# Schaltplan_6011057_Tamme.net
KiCad netlist of a schematic drawn in EAGLE
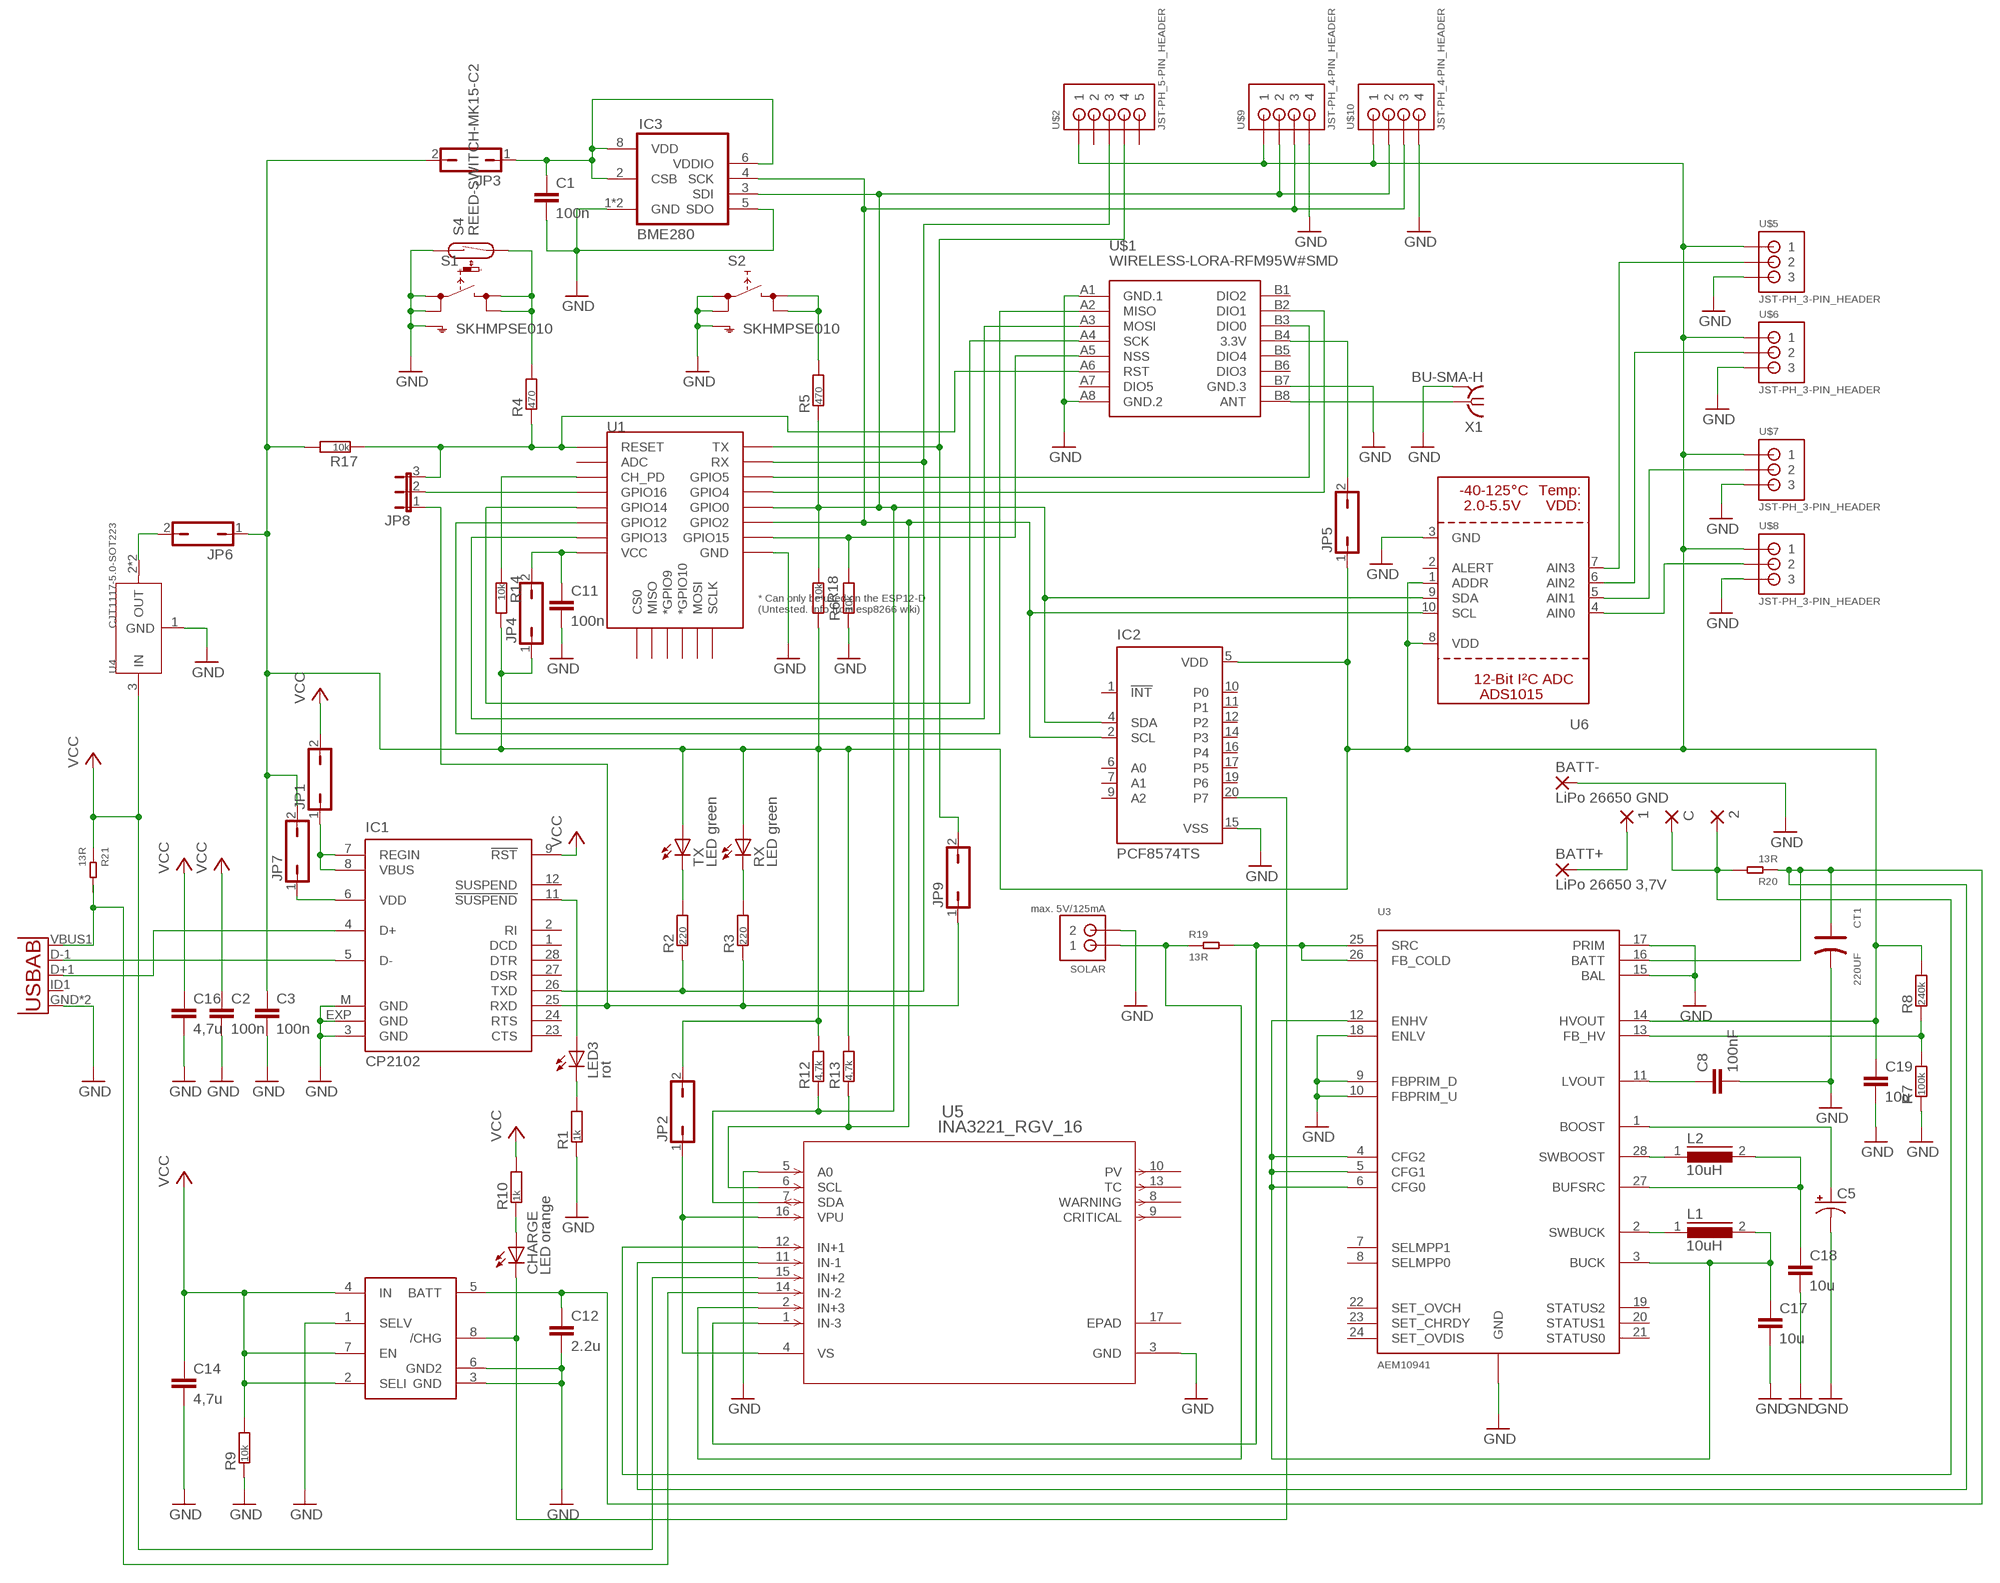
[diagram p0: schematic, sheet 1]

(export (version "E")
  (design (tool "Eeschema 10.0.6"))
  (components
    (comp (ref "1")
      (value "WIREPAD2,54/1,0")
      (footprint "eagle-import:2,54_1,0")
      (libsource (lib "eagle-import") (part "WIREPAD2,54/1,0"))
    )
    (comp (ref "2")
      (value "WIREPAD2,54/1,0")
      (footprint "eagle-import:2,54_1,0")
      (libsource (lib "eagle-import") (part "WIREPAD2,54/1,0"))
    )
    (comp (ref "BATT+")
      (value "LiPo 26650 3,7V")
      (footprint "eagle-import:4,16O1,6")
      (libsource (lib "eagle-import") (part "WIREPAD4,16O1,6"))
    )
    (comp (ref "BATT-")
      (value "LiPo 26650 GND")
      (footprint "eagle-import:4,16O1,6")
      (libsource (lib "eagle-import") (part "WIREPAD4,16O1,6"))
    )
    (comp (ref "C")
      (value "WIREPAD2,54/1,0")
      (footprint "eagle-import:2,54_1,0")
      (libsource (lib "eagle-import") (part "WIREPAD2,54/1,0"))
    )
    (comp (ref "C1")
      (value "100n")
      (footprint "eagle-import:RESC0805_M")
      (libsource (lib "eagle-import") (part "CAPACITOR_0805_M"))
    )
    (comp (ref "C2")
      (value "100n")
      (footprint "eagle-import:RESC0805_M")
      (libsource (lib "eagle-import") (part "CAPACITOR_0805_M"))
    )
    (comp (ref "C3")
      (value "100n")
      (footprint "eagle-import:RESC0805_M")
      (libsource (lib "eagle-import") (part "CAPACITOR_0805_M"))
    )
    (comp (ref "C5")
      (value "CPOL-USB/3528-21W")
      (footprint "eagle-import:B_3528-21W")
      (libsource (lib "eagle-import") (part "CPOL-USB/3528-21W"))
    )
    (comp (ref "C8")
      (value "100nF")
      (footprint "eagle-import:C1206")
      (libsource (lib "eagle-import") (part "CC1206"))
    )
    (comp (ref "C11")
      (value "100n")
      (footprint "eagle-import:RESC0805_M")
      (libsource (lib "eagle-import") (part "CAPACITOR_0805_M"))
    )
    (comp (ref "C12")
      (value "2.2u")
      (footprint "eagle-import:C1812")
      (libsource (lib "eagle-import") (part "C-EUC1812"))
    )
    (comp (ref "C14")
      (value "4,7u")
      (footprint "eagle-import:C1812")
      (libsource (lib "eagle-import") (part "C-EUC1812"))
    )
    (comp (ref "C16")
      (value "4,7u")
      (footprint "eagle-import:C1812")
      (libsource (lib "eagle-import") (part "C-EUC1812"))
    )
    (comp (ref "C17")
      (value "10u")
      (footprint "eagle-import:C1812")
      (libsource (lib "eagle-import") (part "C-EUC1812"))
    )
    (comp (ref "C18")
      (value "10u")
      (footprint "eagle-import:C1812")
      (libsource (lib "eagle-import") (part "C-EUC1812"))
    )
    (comp (ref "C19")
      (value "10u")
      (footprint "eagle-import:C1812")
      (libsource (lib "eagle-import") (part "C-EUC1812"))
    )
    (comp (ref "CHARGE")
      (value "LED orange")
      (footprint "eagle-import:1206")
      (libsource (lib "eagle-import") (part "LEDSMT1206"))
    )
    (comp (ref "CT1")
      (value "220UF")
      (footprint "eagle-import:ELECTRO-SMD-C-6MM")
      (fields (field (name "MPN") "CS1E221M-CRE77"))
      (libsource (lib "eagle-import") (part "ALUMINUM-SMD-220UF-16V(D6.3-H7.7MM)"))
    )
    (comp (ref "IC1")
      (value "CP2102")
      (footprint "eagle-import:MLP28")
      (fields (field (name "MF") "FARNELL") (field (name "MPN") "CP2102-GM"))
      (libsource (lib "eagle-import") (part "CP2102"))
    )
    (comp (ref "IC2")
      (value "PCF8574TS")
      (footprint "eagle-import:SSOP20")
      (fields (field (name "MPN") "PCF8574TS/3,118"))
      (libsource (lib "eagle-import") (part "PCF8574TS"))
    )
    (comp (ref "IC3")
      (value "BME280")
      (footprint "eagle-import:BME280")
      (libsource (lib "eagle-import") (part "BME280"))
    )
    (comp (ref "JP1")
      (value "JP1Q")
      (footprint "eagle-import:JP1")
      (libsource (lib "eagle-import") (part "JP1Q"))
    )
    (comp (ref "JP2")
      (value "JP1Q")
      (footprint "eagle-import:JP1")
      (libsource (lib "eagle-import") (part "JP1Q"))
    )
    (comp (ref "JP3")
      (value "JP1Q")
      (footprint "eagle-import:JP1")
      (libsource (lib "eagle-import") (part "JP1Q"))
    )
    (comp (ref "JP4")
      (value "JP1Q")
      (footprint "eagle-import:JP1")
      (libsource (lib "eagle-import") (part "JP1Q"))
    )
    (comp (ref "JP5")
      (value "JP1Q")
      (footprint "eagle-import:JP1")
      (libsource (lib "eagle-import") (part "JP1Q"))
    )
    (comp (ref "JP6")
      (value "JP1Q")
      (footprint "eagle-import:JP1")
      (libsource (lib "eagle-import") (part "JP1Q"))
    )
    (comp (ref "JP7")
      (value "JP1Q")
      (footprint "eagle-import:JP1")
      (libsource (lib "eagle-import") (part "JP1Q"))
    )
    (comp (ref "JP8")
      (value "JP2E")
      (footprint "eagle-import:JP2")
      (libsource (lib "eagle-import") (part "JP2E"))
    )
    (comp (ref "JP9")
      (value "JP1Q")
      (footprint "eagle-import:JP1")
      (libsource (lib "eagle-import") (part "JP1Q"))
    )
    (comp (ref "L1")
      (value "10uH")
      (footprint "eagle-import:DR74")
      (libsource (lib "eagle-import") (part "DR74"))
    )
    (comp (ref "L2")
      (value "10uH")
      (footprint "eagle-import:DR74")
      (libsource (lib "eagle-import") (part "DR74"))
    )
    (comp (ref "LED3")
      (value "rot")
      (footprint "eagle-import:1206")
      (libsource (lib "eagle-import") (part "LEDSMT1206"))
    )
    (comp (ref "R1")
      (value "1k")
      (footprint "eagle-import:RESC0805_M")
      (libsource (lib "eagle-import") (part "RESISTOR_0805_M"))
    )
    (comp (ref "R2")
      (value "220")
      (footprint "eagle-import:RESC0805_M")
      (libsource (lib "eagle-import") (part "RESISTOR_0805_M"))
    )
    (comp (ref "R3")
      (value "220")
      (footprint "eagle-import:RESC0805_M")
      (libsource (lib "eagle-import") (part "RESISTOR_0805_M"))
    )
    (comp (ref "R4")
      (value "470")
      (footprint "eagle-import:RESC0805_M")
      (libsource (lib "eagle-import") (part "RESISTOR_0805_M"))
    )
    (comp (ref "R5")
      (value "470")
      (footprint "eagle-import:RESC0805_M")
      (libsource (lib "eagle-import") (part "RESISTOR_0805_M"))
    )
    (comp (ref "R6")
      (value "10k")
      (footprint "eagle-import:RESC0805_M")
      (libsource (lib "eagle-import") (part "RESISTOR_0805_M"))
    )
    (comp (ref "R7")
      (value "100k")
      (footprint "eagle-import:RESC0805_M")
      (libsource (lib "eagle-import") (part "RESISTOR_0805_M"))
    )
    (comp (ref "R8")
      (value "240k")
      (footprint "eagle-import:RESC0805_M")
      (libsource (lib "eagle-import") (part "RESISTOR_0805_M"))
    )
    (comp (ref "R9")
      (value "10k")
      (footprint "eagle-import:RESC0805_M")
      (libsource (lib "eagle-import") (part "RESISTOR_0805_M"))
    )
    (comp (ref "R10")
      (value "1k")
      (footprint "eagle-import:RESC0805_M")
      (libsource (lib "eagle-import") (part "RESISTOR_0805_M"))
    )
    (comp (ref "R12")
      (value "4,7k")
      (footprint "eagle-import:RESC0805_M")
      (libsource (lib "eagle-import") (part "RESISTOR_0805_M"))
    )
    (comp (ref "R13")
      (value "4,7k")
      (footprint "eagle-import:RESC0805_M")
      (libsource (lib "eagle-import") (part "RESISTOR_0805_M"))
    )
    (comp (ref "R14")
      (value "10k")
      (footprint "eagle-import:RESC0805_M")
      (libsource (lib "eagle-import") (part "RESISTOR_0805_M"))
    )
    (comp (ref "R17")
      (value "10k")
      (footprint "eagle-import:RESC0805_M")
      (libsource (lib "eagle-import") (part "RESISTOR_0805_M"))
    )
    (comp (ref "R18")
      (value "10k")
      (footprint "eagle-import:RESC0805_M")
      (libsource (lib "eagle-import") (part "RESISTOR_0805_M"))
    )
    (comp (ref "R19")
      (value "13R")
      (footprint "eagle-import:R1206")
      (fields (field (name "MPN") "RC1206JR-0713RL"))
      (libsource (lib "eagle-import") (part "SMD-RES-13R-5%-1/4W(1206)"))
    )
    (comp (ref "R20")
      (value "13R")
      (footprint "eagle-import:R1206")
      (fields (field (name "MPN") "RC1206JR-0713RL"))
      (libsource (lib "eagle-import") (part "SMD-RES-13R-5%-1/4W(1206)"))
    )
    (comp (ref "R21")
      (value "13R")
      (footprint "eagle-import:R1206")
      (fields (field (name "MPN") "RC1206JR-0713RL"))
      (libsource (lib "eagle-import") (part "SMD-RES-13R-5%-1/4W(1206)"))
    )
    (comp (ref "RX")
      (value "LED green")
      (footprint "eagle-import:1206")
      (libsource (lib "eagle-import") (part "LEDSMT1206"))
    )
    (comp (ref "S1")
      (value "SKHMPSE010")
      (footprint "eagle-import:SKHMPXE010")
      (libsource (lib "eagle-import") (part "SKHMPE010S"))
    )
    (comp (ref "S2")
      (value "SKHMPSE010")
      (footprint "eagle-import:SKHMPXE010")
      (libsource (lib "eagle-import") (part "SKHMPE010S"))
    )
    (comp (ref "S4")
      (value "REED-SWITCH-MK15-C2")
      (footprint "eagle-import:MK15")
      (fields (field (name "MF") "MEDER") (field (name "MPN") "MK15-C-2"))
      (libsource (lib "eagle-import") (part "REED-SWITCH-MK15-C2"))
    )
    (comp (ref "SOLAR")
      (value "max. 5V/125mA")
      (footprint "eagle-import:JST_B2B-PH_HEADER")
      (libsource (lib "eagle-import") (part "JST-PH_2-PIN_HEADER"))
    )
    (comp (ref "TX")
      (value "LED green")
      (footprint "eagle-import:1206")
      (libsource (lib "eagle-import") (part "LEDSMT1206"))
    )
    (comp (ref "U$1")
      (value "WIRELESS-LORA-RFM95W#SMD")
      (footprint "eagle-import:WIRELESS-LORA-RFM95W#SMD")
      (libsource (lib "eagle-import") (part "WIRELESS-LORA-RFM95W#SMD"))
    )
    (comp (ref "U$2")
      (value "JST-PH_5-PIN_HEADER")
      (footprint "eagle-import:JST_B5B-PH_HEADER")
      (libsource (lib "eagle-import") (part "JST-PH_5-PIN_HEADER"))
    )
    (comp (ref "U$3")
      (value "MAX1811SO8")
      (footprint "eagle-import:SO08")
      (libsource (lib "eagle-import") (part "MAX1811SO8"))
    )
    (comp (ref "U$5")
      (value "JST-PH_3-PIN_HEADER")
      (footprint "eagle-import:JST_B3B-PH_HEADER")
      (libsource (lib "eagle-import") (part "JST-PH_3-PIN_HEADER"))
    )
    (comp (ref "U$6")
      (value "JST-PH_3-PIN_HEADER")
      (footprint "eagle-import:JST_B3B-PH_HEADER")
      (libsource (lib "eagle-import") (part "JST-PH_3-PIN_HEADER"))
    )
    (comp (ref "U$7")
      (value "JST-PH_3-PIN_HEADER")
      (footprint "eagle-import:JST_B3B-PH_HEADER")
      (libsource (lib "eagle-import") (part "JST-PH_3-PIN_HEADER"))
    )
    (comp (ref "U$8")
      (value "JST-PH_3-PIN_HEADER")
      (footprint "eagle-import:JST_B3B-PH_HEADER")
      (libsource (lib "eagle-import") (part "JST-PH_3-PIN_HEADER"))
    )
    (comp (ref "U$9")
      (value "JST-PH_4-PIN_HEADER")
      (footprint "eagle-import:JST_B4B-PH_HEADER")
      (libsource (lib "eagle-import") (part "JST-PH_4-PIN_HEADER"))
    )
    (comp (ref "U$10")
      (value "JST-PH_4-PIN_HEADER")
      (footprint "eagle-import:JST_B4B-PH_HEADER")
      (libsource (lib "eagle-import") (part "JST-PH_4-PIN_HEADER"))
    )
    (comp (ref "U1")
      (value "ESP12ESMD")
      (footprint "eagle-import:ESP12E-SMD")
      (libsource (lib "eagle-import") (part "ESP12ESMD"))
    )
    (comp (ref "U2")
      (value "USB\"\"")
      (footprint "eagle-import:USB-MICRO-SMD")
      (libsource (lib "eagle-import") (part "USB{dblquote}{dblquote}"))
    )
    (comp (ref "U3")
      (value "AEM10941")
      (footprint "eagle-import:QFN28_5X5_05PITCH")
      (libsource (lib "eagle-import") (part "AEM10941"))
    )
    (comp (ref "U4")
      (value "CJT1117-5.0-SOT223")
      (footprint "eagle-import:SOT-223")
      (fields (field (name "MPN") "CJT1117-5.0"))
      (libsource (lib "eagle-import") (part "PMIC-CJT1117-5.0(SOT223)"))
    )
    (comp (ref "U5")
      (value "INA3221_RGV_16")
      (footprint "eagle-import:RGV16_2P16X2P16")
      (fields
        (field (name "GENERIC_PART_NUMBER") "INA3221")
        (field (name "MANUFACTURER") "Texas Instruments")
      )
      (libsource (lib "eagle-import") (part "INA3221_RGV_16"))
    )
    (comp (ref "U6")
      (value "ADC_ADS1015")
      (footprint "eagle-import:MSOP10")
      (libsource (lib "eagle-import") (part "ADC_ADS1015"))
    )
    (comp (ref "X1")
      (value "BU-SMA-H")
      (footprint "eagle-import:BU-SMA-H")
      (libsource (lib "eagle-import") (part "BU-SMA-H"))
    )
  )
  (nets
    (net (code "1") (name "GND") (class "Default")
      (node (ref "BATT-") (pin "1") (pinfunction "P_1") (pintype "passive"))
      (node (ref "C1") (pin "2") (pinfunction "2_2") (pintype "passive"))
      (node (ref "C11") (pin "2") (pinfunction "2_2") (pintype "passive"))
      (node (ref "C12") (pin "2") (pinfunction "2_2") (pintype "passive"))
      (node (ref "C14") (pin "2") (pinfunction "2_2") (pintype "passive"))
      (node (ref "C16") (pin "2") (pinfunction "2_2") (pintype "passive"))
      (node (ref "C17") (pin "2") (pinfunction "2_2") (pintype "passive"))
      (node (ref "C18") (pin "2") (pinfunction "2_2") (pintype "passive"))
      (node (ref "C19") (pin "2") (pinfunction "2_2") (pintype "passive"))
      (node (ref "C2") (pin "2") (pinfunction "2_2") (pintype "passive"))
      (node (ref "C3") (pin "2") (pinfunction "2_2") (pintype "passive"))
      (node (ref "C5") (pin "-") (pinfunction "-_-") (pintype "passive"))
      (node (ref "C8") (pin "2") (pinfunction "2_2") (pintype "passive"))
      (node (ref "CT1") (pin "-") (pinfunction "-_-") (pintype "passive"))
      (node (ref "IC1") (pin "3") (pinfunction "GND_3") (pintype "power_in"))
      (node (ref "IC1") (pin "EXP") (pinfunction "GND_EXP") (pintype "power_in"))
      (node (ref "IC1") (pin "M") (pinfunction "GND_M") (pintype "power_in"))
      (node (ref "IC2") (pin "15") (pinfunction "VSS_15") (pintype "power_in"))
      (node (ref "IC3") (pin "1") (pinfunction "GND_1") (pintype "power_in"))
      (node (ref "IC3") (pin "5") (pinfunction "SDO_5") (pintype "input"))
      (node (ref "IC3") (pin "7") (pinfunction "GND_7") (pintype "power_in"))
      (node (ref "R1") (pin "1") (pinfunction "1_1") (pintype "passive"))
      (node (ref "R6") (pin "1") (pinfunction "1_1") (pintype "passive"))
      (node (ref "R7") (pin "1") (pinfunction "1_1") (pintype "passive"))
      (node (ref "R9") (pin "1") (pinfunction "1_1") (pintype "passive"))
      (node (ref "S1") (pin "1") (pinfunction "1.1_1") (pintype "passive"))
      (node (ref "S1") (pin "2") (pinfunction "1.2_2") (pintype "passive"))
      (node (ref "S1") (pin "5") (pinfunction "SH_5") (pintype "passive"))
      (node (ref "S2") (pin "1") (pinfunction "1.1_1") (pintype "passive"))
      (node (ref "S2") (pin "2") (pinfunction "1.2_2") (pintype "passive"))
      (node (ref "S2") (pin "5") (pinfunction "SH_5") (pintype "passive"))
      (node (ref "S4") (pin "1") (pinfunction "1_1") (pintype "passive"))
      (node (ref "SOLAR") (pin "P2") (pinfunction "2_P2") (pintype "bidirectional"))
      (node (ref "U$1") (pin "A1") (pinfunction "GND.1_A1") (pintype "power_in"))
      (node (ref "U$1") (pin "A8") (pinfunction "GND.2_A8") (pintype "power_in"))
      (node (ref "U$1") (pin "B7") (pinfunction "GND.3_B7") (pintype "power_in"))
      (node (ref "U$10") (pin "P4") (pinfunction "4_P4") (pintype "bidirectional"))
      (node (ref "U$3") (pin "1") (pinfunction "SELV_1") (pintype "bidirectional"))
      (node (ref "U$3") (pin "3") (pinfunction "GND_3") (pintype "bidirectional"))
      (node (ref "U$3") (pin "6") (pinfunction "GND2_6") (pintype "bidirectional"))
      (node (ref "U$5") (pin "P3") (pinfunction "3_P3") (pintype "bidirectional"))
      (node (ref "U$6") (pin "P3") (pinfunction "3_P3") (pintype "bidirectional"))
      (node (ref "U$7") (pin "P3") (pinfunction "3_P3") (pintype "bidirectional"))
      (node (ref "U$8") (pin "P3") (pinfunction "3_P3") (pintype "bidirectional"))
      (node (ref "U$9") (pin "P4") (pinfunction "4_P4") (pintype "bidirectional"))
      (node (ref "U1") (pin "GND") (pinfunction "GND_GND") (pintype "bidirectional"))
      (node (ref "U2") (pin "GND") (pinfunction "GND_GND") (pintype "bidirectional"))
      (node (ref "U2") (pin "GND1") (pinfunction "GND_GND1") (pintype "bidirectional"))
      (node (ref "U3") (pin "10") (pinfunction "FBPRIM_U_10") (pintype "bidirectional"))
      (node (ref "U3") (pin "15") (pinfunction "BAL_15") (pintype "bidirectional"))
      (node (ref "U3") (pin "17") (pinfunction "PRIM_17") (pintype "bidirectional"))
      (node (ref "U3") (pin "18") (pinfunction "ENLV_18") (pintype "input"))
      (node (ref "U3") (pin "9") (pinfunction "FBPRIM_D_9") (pintype "bidirectional"))
      (node (ref "U3") (pin "GND") (pinfunction "GND_GND") (pintype "power_in"))
      (node (ref "U3") (pin "GND1") (pinfunction "GND_GND1") (pintype "power_in"))
      (node (ref "U3") (pin "GND2") (pinfunction "GND_GND2") (pintype "power_in"))
      (node (ref "U3") (pin "GND3") (pinfunction "GND_GND3") (pintype "power_in"))
      (node (ref "U3") (pin "GND4") (pinfunction "GND_GND4") (pintype "power_in"))
      (node (ref "U3") (pin "GND5") (pinfunction "GND_GND5") (pintype "power_in"))
      (node (ref "U4") (pin "1") (pinfunction "GND_1") (pintype "bidirectional"))
      (node (ref "U5") (pin "3") (pinfunction "GND_3") (pintype "power_in"))
      (node (ref "U5") (pin "5") (pinfunction "A0_5") (pintype "input"))
      (node (ref "U6") (pin "3") (pinfunction "GND_3") (pintype "bidirectional"))
      (node (ref "X1") (pin "2") (pinfunction "2_2") (pintype "passive"))
      (node (ref "X1") (pin "3") (pinfunction "2_3") (pintype "passive"))
      (node (ref "X1") (pin "4") (pinfunction "2_4") (pintype "passive"))
      (node (ref "X1") (pin "5") (pinfunction "2_5") (pintype "passive"))
    )
    (net (code "2") (name "Net-(1-P)") (class "Default")
      (node (ref "1") (pin "1") (pinfunction "P_1") (pintype "passive"))
      (node (ref "BATT+") (pin "1") (pinfunction "P_1") (pintype "passive"))
    )
    (net (code "3") (name "Net-(2-P)") (class "Default")
      (node (ref "2") (pin "1") (pinfunction "P_1") (pintype "passive"))
      (node (ref "C") (pin "1") (pinfunction "P_1") (pintype "passive"))
      (node (ref "R20") (pin "2") (pinfunction "2_2") (pintype "passive"))
      (node (ref "U5") (pin "12") (pinfunction "IN+1_12") (pintype "input"))
    )
    (net (code "4") (name "Net-(C11-Pad1)") (class "Default")
      (node (ref "C11") (pin "1") (pinfunction "1_1") (pintype "passive"))
      (node (ref "JP4") (pin "2") (pinfunction "2_2") (pintype "passive"))
      (node (ref "U1") (pin "VCC") (pinfunction "VCC_VCC") (pintype "bidirectional"))
    )
    (net (code "5") (name "Net-(CHARGE-PadA)") (class "Default")
      (node (ref "CHARGE") (pin "A") (pinfunction "A_A") (pintype "passive"))
      (node (ref "R10") (pin "1") (pinfunction "1_1") (pintype "passive"))
    )
    (net (code "6") (name "Net-(IC1-D+)") (class "Default")
      (node (ref "IC1") (pin "4") (pinfunction "D+_4") (pintype "bidirectional"))
      (node (ref "U2") (pin "D+1") (pinfunction "D+_D+1") (pintype "bidirectional"))
    )
    (net (code "7") (name "Net-(IC1-D-)") (class "Default")
      (node (ref "IC1") (pin "5") (pinfunction "D-_5") (pintype "bidirectional"))
      (node (ref "U2") (pin "D-1") (pinfunction "D-_D-1") (pintype "bidirectional"))
    )
    (net (code "8") (name "Net-(IC1-REGIN)") (class "Default")
      (node (ref "IC1") (pin "7") (pinfunction "REGIN_7") (pintype "passive"))
      (node (ref "IC1") (pin "8") (pinfunction "VBUS_8") (pintype "input"))
      (node (ref "JP1") (pin "1") (pinfunction "1_1") (pintype "passive"))
    )
    (net (code "9") (name "Net-(IC1-RXD)") (class "Default")
      (node (ref "IC1") (pin "25") (pinfunction "RXD_25") (pintype "input"))
      (node (ref "JP8") (pin "1") (pinfunction "1_1") (pintype "passive"))
      (node (ref "JP9") (pin "1") (pinfunction "1_1") (pintype "passive"))
      (node (ref "R3") (pin "1") (pinfunction "1_1") (pintype "passive"))
    )
    (net (code "10") (name "Net-(IC1-TXD)") (class "Default")
      (node (ref "IC1") (pin "26") (pinfunction "TXD_26") (pintype "output"))
      (node (ref "R2") (pin "1") (pinfunction "1_1") (pintype "passive"))
      (node (ref "U$2") (pin "P3") (pinfunction "3_P3") (pintype "bidirectional"))
      (node (ref "U1") (pin "RXD0") (pinfunction "RX_RXD0") (pintype "bidirectional"))
    )
    (net (code "11") (name "Net-(IC1-VDD)") (class "Default")
      (node (ref "IC1") (pin "6") (pinfunction "VDD_6") (pintype "power_in"))
      (node (ref "JP7") (pin "1") (pinfunction "1_1") (pintype "passive"))
    )
    (net (code "12") (name "Net-(IC1-~{SUSPEND})") (class "Default")
      (node (ref "IC1") (pin "11") (pinfunction "~{SUSPEND}_11") (pintype "output"))
      (node (ref "LED3") (pin "A") (pinfunction "A_A") (pintype "passive"))
    )
    (net (code "13") (name "Net-(IC2-P7)") (class "Default")
      (node (ref "CHARGE") (pin "C") (pinfunction "C_C") (pintype "passive"))
      (node (ref "IC2") (pin "20") (pinfunction "P7_20") (pintype "bidirectional"))
      (node (ref "U$3") (pin "8") (pinfunction "/CHG_8") (pintype "bidirectional"))
    )
    (net (code "14") (name "Net-(IC2-SCL)") (class "Default")
      (node (ref "IC2") (pin "2") (pinfunction "SCL_2") (pintype "input"))
      (node (ref "IC3") (pin "4") (pinfunction "SCK_4") (pintype "bidirectional"))
      (node (ref "R13") (pin "1") (pinfunction "1_1") (pintype "passive"))
      (node (ref "U$10") (pin "P3") (pinfunction "3_P3") (pintype "bidirectional"))
      (node (ref "U$9") (pin "P3") (pinfunction "3_P3") (pintype "bidirectional"))
      (node (ref "U1") (pin "GPIO2") (pinfunction "GPIO2_GPIO2") (pintype "bidirectional"))
      (node (ref "U5") (pin "6") (pinfunction "SCL_6") (pintype "input"))
      (node (ref "U6") (pin "10") (pinfunction "SCL_10") (pintype "bidirectional"))
    )
    (net (code "15") (name "Net-(IC2-SDA)") (class "Default")
      (node (ref "IC2") (pin "4") (pinfunction "SDA_4") (pintype "bidirectional"))
      (node (ref "IC3") (pin "3") (pinfunction "SDI_3") (pintype "bidirectional"))
      (node (ref "R12") (pin "1") (pinfunction "1_1") (pintype "passive"))
      (node (ref "R18") (pin "1") (pinfunction "1_1") (pintype "passive"))
      (node (ref "R5") (pin "1") (pinfunction "1_1") (pintype "passive"))
      (node (ref "U$10") (pin "P2") (pinfunction "2_P2") (pintype "bidirectional"))
      (node (ref "U$9") (pin "P2") (pinfunction "2_P2") (pintype "bidirectional"))
      (node (ref "U1") (pin "GPIO0") (pinfunction "GPIO0_GPIO0") (pintype "bidirectional"))
      (node (ref "U5") (pin "7") (pinfunction "SDA_7") (pintype "bidirectional"))
      (node (ref "U6") (pin "9") (pinfunction "SDA_9") (pintype "bidirectional"))
    )
    (net (code "16") (name "Net-(IC2-VDD)") (class "Default")
      (node (ref "C19") (pin "1") (pinfunction "1_1") (pintype "passive"))
      (node (ref "C3") (pin "1") (pinfunction "1_1") (pintype "passive"))
      (node (ref "IC2") (pin "5") (pinfunction "VDD_5") (pintype "power_in"))
      (node (ref "JP2") (pin "2") (pinfunction "2_2") (pintype "passive"))
      (node (ref "JP3") (pin "2") (pinfunction "2_2") (pintype "passive"))
      (node (ref "JP4") (pin "1") (pinfunction "1_1") (pintype "passive"))
      (node (ref "JP5") (pin "1") (pinfunction "1_1") (pintype "passive"))
      (node (ref "JP6") (pin "1") (pinfunction "1_1") (pintype "passive"))
      (node (ref "JP7") (pin "2") (pinfunction "2_2") (pintype "passive"))
      (node (ref "R12") (pin "2") (pinfunction "2_2") (pintype "passive"))
      (node (ref "R13") (pin "2") (pinfunction "2_2") (pintype "passive"))
      (node (ref "R14") (pin "2") (pinfunction "2_2") (pintype "passive"))
      (node (ref "R17") (pin "2") (pinfunction "2_2") (pintype "passive"))
      (node (ref "R18") (pin "2") (pinfunction "2_2") (pintype "passive"))
      (node (ref "R8") (pin "2") (pinfunction "2_2") (pintype "passive"))
      (node (ref "RX") (pin "A") (pinfunction "A_A") (pintype "passive"))
      (node (ref "TX") (pin "A") (pinfunction "A_A") (pintype "passive"))
      (node (ref "U$10") (pin "P1") (pinfunction "1_P1") (pintype "bidirectional"))
      (node (ref "U$2") (pin "P1") (pinfunction "1_P1") (pintype "bidirectional"))
      (node (ref "U$5") (pin "P1") (pinfunction "1_P1") (pintype "bidirectional"))
      (node (ref "U$6") (pin "P1") (pinfunction "1_P1") (pintype "bidirectional"))
      (node (ref "U$7") (pin "P1") (pinfunction "1_P1") (pintype "bidirectional"))
      (node (ref "U$8") (pin "P1") (pinfunction "1_P1") (pintype "bidirectional"))
      (node (ref "U$9") (pin "P1") (pinfunction "1_P1") (pintype "bidirectional"))
      (node (ref "U3") (pin "14") (pinfunction "HVOUT_14") (pintype "output"))
      (node (ref "U6") (pin "1") (pinfunction "ADDR_1") (pintype "bidirectional"))
      (node (ref "U6") (pin "8") (pinfunction "VDD_8") (pintype "bidirectional"))
    )
    (net (code "17") (name "Net-(IC3-CSB)") (class "Default")
      (node (ref "C1") (pin "1") (pinfunction "1_1") (pintype "passive"))
      (node (ref "IC3") (pin "2") (pinfunction "CSB_2") (pintype "input"))
      (node (ref "IC3") (pin "6") (pinfunction "VDDIO_6") (pintype "power_in"))
      (node (ref "IC3") (pin "8") (pinfunction "VDD_8") (pintype "power_in"))
      (node (ref "JP3") (pin "1") (pinfunction "1_1") (pintype "passive"))
    )
    (net (code "18") (name "Net-(JP6-Pad2)") (class "Default")
      (node (ref "JP6") (pin "2") (pinfunction "2_2") (pintype "passive"))
      (node (ref "U4") (pin "2") (pinfunction "OUT_2") (pintype "bidirectional"))
      (node (ref "U4") (pin "TER") (pinfunction "OUT_TER") (pintype "bidirectional"))
    )
    (net (code "19") (name "Net-(JP8-Pad2)") (class "Default")
      (node (ref "JP8") (pin "2") (pinfunction "2_2") (pintype "passive"))
      (node (ref "U1") (pin "GPIO16") (pinfunction "GPIO16_GPIO16") (pintype "bidirectional"))
    )
    (net (code "20") (name "Net-(LED3-PadC)") (class "Default")
      (node (ref "LED3") (pin "C") (pinfunction "C_C") (pintype "passive"))
      (node (ref "R1") (pin "2") (pinfunction "2_2") (pintype "passive"))
    )
    (net (code "21") (name "Net-(R2-Pad2)") (class "Default")
      (node (ref "R2") (pin "2") (pinfunction "2_2") (pintype "passive"))
      (node (ref "TX") (pin "C") (pinfunction "C_C") (pintype "passive"))
    )
    (net (code "22") (name "Net-(R3-Pad2)") (class "Default")
      (node (ref "R3") (pin "2") (pinfunction "2_2") (pintype "passive"))
      (node (ref "RX") (pin "C") (pinfunction "C_C") (pintype "passive"))
    )
    (net (code "23") (name "Net-(R14-Pad1)") (class "Default")
      (node (ref "R14") (pin "1") (pinfunction "1_1") (pintype "passive"))
      (node (ref "U1") (pin "CH_PD") (pinfunction "CH_PD_CH_PD") (pintype "bidirectional"))
    )
    (net (code "24") (name "Net-(S1-2.1)") (class "Default")
      (node (ref "R4") (pin "2") (pinfunction "2_2") (pintype "passive"))
      (node (ref "S1") (pin "3") (pinfunction "2.1_3") (pintype "passive"))
      (node (ref "S1") (pin "4") (pinfunction "2.2_4") (pintype "passive"))
      (node (ref "S4") (pin "2") (pinfunction "2_2") (pintype "passive"))
    )
    (net (code "25") (name "Net-(S2-2.1)") (class "Default")
      (node (ref "R5") (pin "2") (pinfunction "2_2") (pintype "passive"))
      (node (ref "S2") (pin "3") (pinfunction "2.1_3") (pintype "passive"))
      (node (ref "S2") (pin "4") (pinfunction "2.2_4") (pintype "passive"))
    )
    (net (code "26") (name "Net-(SOLAR-1)") (class "Default")
      (node (ref "R19") (pin "1") (pinfunction "1_1") (pintype "passive"))
      (node (ref "SOLAR") (pin "P1") (pinfunction "1_P1") (pintype "bidirectional"))
      (node (ref "U5") (pin "2") (pinfunction "IN+3_2") (pintype "input"))
    )
    (net (code "27") (name "Net-(U$1-3.3V)") (class "Default")
      (node (ref "JP5") (pin "2") (pinfunction "2_2") (pintype "passive"))
      (node (ref "U$1") (pin "B4") (pinfunction "3.3V_B4") (pintype "power_in"))
    )
    (net (code "28") (name "Net-(U$1-ANT)") (class "Default")
      (node (ref "U$1") (pin "B8") (pinfunction "ANT_B8") (pintype "passive"))
      (node (ref "X1") (pin "1") (pinfunction "1_1") (pintype "passive"))
    )
    (net (code "29") (name "Net-(U$1-DIO0)") (class "Default")
      (node (ref "U$1") (pin "B3") (pinfunction "DIO0_B3") (pintype "bidirectional"))
      (node (ref "U1") (pin "GPIO5") (pinfunction "GPIO5_GPIO5") (pintype "bidirectional"))
    )
    (net (code "30") (name "Net-(U$1-DIO1)") (class "Default")
      (node (ref "U$1") (pin "B2") (pinfunction "DIO1_B2") (pintype "bidirectional"))
      (node (ref "U1") (pin "GPIO4") (pinfunction "GPIO4_GPIO4") (pintype "bidirectional"))
    )
    (net (code "31") (name "Net-(U$1-MISO)") (class "Default")
      (node (ref "U$1") (pin "A2") (pinfunction "MISO_A2") (pintype "bidirectional"))
      (node (ref "U1") (pin "GPIO12") (pinfunction "GPIO12_GPIO12") (pintype "bidirectional"))
    )
    (net (code "32") (name "Net-(U$1-MOSI)") (class "Default")
      (node (ref "U$1") (pin "A3") (pinfunction "MOSI_A3") (pintype "bidirectional"))
      (node (ref "U1") (pin "GPIO13") (pinfunction "GPIO13_GPIO13") (pintype "bidirectional"))
    )
    (net (code "33") (name "Net-(U$1-NSS)") (class "Default")
      (node (ref "R6") (pin "2") (pinfunction "2_2") (pintype "passive"))
      (node (ref "U$1") (pin "A5") (pinfunction "NSS_A5") (pintype "bidirectional"))
      (node (ref "U1") (pin "GPIO15") (pinfunction "GPIO15_GPIO15") (pintype "bidirectional"))
    )
    (net (code "34") (name "Net-(U$1-RST)") (class "Default")
      (node (ref "JP8") (pin "3") (pinfunction "3_3") (pintype "passive"))
      (node (ref "R17") (pin "1") (pinfunction "1_1") (pintype "passive"))
      (node (ref "R4") (pin "1") (pinfunction "1_1") (pintype "passive"))
      (node (ref "U$1") (pin "A6") (pinfunction "RST_A6") (pintype "bidirectional"))
      (node (ref "U1") (pin "RESET") (pinfunction "RESET_RESET") (pintype "bidirectional"))
    )
    (net (code "35") (name "Net-(U$1-SCK)") (class "Default")
      (node (ref "U$1") (pin "A4") (pinfunction "SCK_A4") (pintype "bidirectional"))
      (node (ref "U1") (pin "GPIO14") (pinfunction "GPIO14_GPIO14") (pintype "bidirectional"))
    )
    (net (code "36") (name "Net-(U$2-4)") (class "Default")
      (node (ref "JP9") (pin "2") (pinfunction "2_2") (pintype "passive"))
      (node (ref "U$2") (pin "P4") (pinfunction "4_P4") (pintype "bidirectional"))
      (node (ref "U1") (pin "TXD0") (pinfunction "TX_TXD0") (pintype "bidirectional"))
    )
    (net (code "37") (name "Net-(U$3-BATT)") (class "Default")
      (node (ref "C12") (pin "1") (pinfunction "1_1") (pintype "passive"))
      (node (ref "CT1") (pin "+") (pinfunction "+_+") (pintype "passive"))
      (node (ref "R20") (pin "1") (pinfunction "1_1") (pintype "passive"))
      (node (ref "U$3") (pin "5") (pinfunction "BATT_5") (pintype "bidirectional"))
      (node (ref "U3") (pin "16") (pinfunction "BATT_16") (pintype "bidirectional"))
      (node (ref "U5") (pin "11") (pinfunction "IN-1_11") (pintype "input"))
    )
    (net (code "38") (name "Net-(U$5-2)") (class "Default")
      (node (ref "U$5") (pin "P2") (pinfunction "2_P2") (pintype "bidirectional"))
      (node (ref "U6") (pin "7") (pinfunction "AIN3_7") (pintype "bidirectional"))
    )
    (net (code "39") (name "Net-(U$6-2)") (class "Default")
      (node (ref "U$6") (pin "P2") (pinfunction "2_P2") (pintype "bidirectional"))
      (node (ref "U6") (pin "6") (pinfunction "AIN2_6") (pintype "bidirectional"))
    )
    (net (code "40") (name "Net-(U$7-2)") (class "Default")
      (node (ref "U$7") (pin "P2") (pinfunction "2_P2") (pintype "bidirectional"))
      (node (ref "U6") (pin "5") (pinfunction "AIN1_5") (pintype "bidirectional"))
    )
    (net (code "41") (name "Net-(U$8-2)") (class "Default")
      (node (ref "U$8") (pin "P2") (pinfunction "2_P2") (pintype "bidirectional"))
      (node (ref "U6") (pin "4") (pinfunction "AIN0_4") (pintype "bidirectional"))
    )
    (net (code "42") (name "Net-(U2-VBUS)") (class "Default")
      (node (ref "U2") (pin "VBUS1") (pinfunction "VBUS_VBUS1") (pintype "bidirectional"))
      (node (ref "U5") (pin "14") (pinfunction "IN-2_14") (pintype "input"))
    )
    (net (code "43") (name "Net-(U3-BOOST)") (class "Default")
      (node (ref "C5") (pin "+") (pinfunction "+_+") (pintype "passive"))
      (node (ref "U3") (pin "1") (pinfunction "BOOST_1") (pintype "bidirectional"))
    )
    (net (code "44") (name "Net-(U3-BUCK)") (class "Default")
      (node (ref "C17") (pin "1") (pinfunction "1_1") (pintype "passive"))
      (node (ref "L1") (pin "2") (pinfunction "2_2") (pintype "passive"))
      (node (ref "U3") (pin "12") (pinfunction "ENHV_12") (pintype "input"))
      (node (ref "U3") (pin "3") (pinfunction "BUCK_3") (pintype "bidirectional"))
      (node (ref "U3") (pin "4") (pinfunction "CFG2_4") (pintype "input"))
      (node (ref "U3") (pin "5") (pinfunction "CFG1_5") (pintype "input"))
      (node (ref "U3") (pin "6") (pinfunction "CFG0_6") (pintype "input"))
    )
    (net (code "45") (name "Net-(U3-BUFSRC)") (class "Default")
      (node (ref "C18") (pin "1") (pinfunction "1_1") (pintype "passive"))
      (node (ref "L2") (pin "2") (pinfunction "2_2") (pintype "passive"))
      (node (ref "U3") (pin "27") (pinfunction "BUFSRC_27") (pintype "bidirectional"))
    )
    (net (code "46") (name "Net-(U3-FB_COLD)") (class "Default")
      (node (ref "R19") (pin "2") (pinfunction "2_2") (pintype "passive"))
      (node (ref "U3") (pin "25") (pinfunction "SRC_25") (pintype "input"))
      (node (ref "U3") (pin "26") (pinfunction "FB_COLD_26") (pintype "bidirectional"))
      (node (ref "U5") (pin "1") (pinfunction "IN-3_1") (pintype "input"))
    )
    (net (code "47") (name "Net-(U3-FB_HV)") (class "Default")
      (node (ref "R7") (pin "2") (pinfunction "2_2") (pintype "passive"))
      (node (ref "R8") (pin "1") (pinfunction "1_1") (pintype "passive"))
      (node (ref "U3") (pin "13") (pinfunction "FB_HV_13") (pintype "input"))
    )
    (net (code "48") (name "Net-(U3-LVOUT)") (class "Default")
      (node (ref "C8") (pin "1") (pinfunction "1_1") (pintype "passive"))
      (node (ref "U3") (pin "11") (pinfunction "LVOUT_11") (pintype "output"))
    )
    (net (code "49") (name "Net-(U3-SWBOOST)") (class "Default")
      (node (ref "L2") (pin "1") (pinfunction "1_1") (pintype "passive"))
      (node (ref "U3") (pin "28") (pinfunction "SWBOOST_28") (pintype "bidirectional"))
    )
    (net (code "50") (name "Net-(U3-SWBUCK)") (class "Default")
      (node (ref "L1") (pin "1") (pinfunction "1_1") (pintype "passive"))
      (node (ref "U3") (pin "2") (pinfunction "SWBUCK_2") (pintype "bidirectional"))
    )
    (net (code "51") (name "Net-(U5-VPU)") (class "Default")
      (node (ref "JP2") (pin "1") (pinfunction "1_1") (pintype "passive"))
      (node (ref "U5") (pin "16") (pinfunction "VPU_16") (pintype "input"))
      (node (ref "U5") (pin "4") (pinfunction "VS_4") (pintype "passive"))
    )
    (net (code "52") (name "VCC") (class "Default")
      (node (ref "C14") (pin "1") (pinfunction "1_1") (pintype "passive"))
      (node (ref "C16") (pin "1") (pinfunction "1_1") (pintype "passive"))
      (node (ref "C2") (pin "1") (pinfunction "1_1") (pintype "passive"))
      (node (ref "IC1") (pin "9") (pinfunction "~{RST}_9") (pintype "bidirectional"))
      (node (ref "JP1") (pin "2") (pinfunction "2_2") (pintype "passive"))
      (node (ref "R10") (pin "2") (pinfunction "2_2") (pintype "passive"))
      (node (ref "R21") (pin "1") (pinfunction "1_1") (pintype "passive"))
      (node (ref "R9") (pin "2") (pinfunction "2_2") (pintype "passive"))
      (node (ref "U$3") (pin "2") (pinfunction "SELI_2") (pintype "bidirectional"))
      (node (ref "U$3") (pin "4") (pinfunction "IN_4") (pintype "bidirectional"))
      (node (ref "U$3") (pin "7") (pinfunction "EN_7") (pintype "bidirectional"))
      (node (ref "U4") (pin "3") (pinfunction "IN_3") (pintype "bidirectional"))
      (node (ref "U5") (pin "15") (pinfunction "IN+2_15") (pintype "input"))
    )
    (net (code "53") (name "unconnected-(IC1-CTS-Pad23)") (class "Default")
      (node (ref "IC1") (pin "23") (pinfunction "CTS_23") (pintype "input"))
    )
    (net (code "54") (name "unconnected-(IC1-DCD-Pad1)") (class "Default")
      (node (ref "IC1") (pin "1") (pinfunction "DCD_1") (pintype "input"))
    )
    (net (code "55") (name "unconnected-(IC1-DSR-Pad27)") (class "Default")
      (node (ref "IC1") (pin "27") (pinfunction "DSR_27") (pintype "input"))
    )
    (net (code "56") (name "unconnected-(IC1-DTR-Pad28)") (class "Default")
      (node (ref "IC1") (pin "28") (pinfunction "DTR_28") (pintype "output"))
    )
    (net (code "57") (name "unconnected-(IC1-RI-Pad2)") (class "Default")
      (node (ref "IC1") (pin "2") (pinfunction "RI_2") (pintype "input"))
    )
    (net (code "58") (name "unconnected-(IC1-RTS-Pad24)") (class "Default")
      (node (ref "IC1") (pin "24") (pinfunction "RTS_24") (pintype "output"))
    )
    (net (code "59") (name "unconnected-(IC1-SUSPEND-Pad12)") (class "Default")
      (node (ref "IC1") (pin "12") (pinfunction "SUSPEND_12") (pintype "output"))
    )
    (net (code "60") (name "unconnected-(IC2-A0-Pad6)") (class "Default")
      (node (ref "IC2") (pin "6") (pinfunction "A0_6") (pintype "input"))
    )
    (net (code "61") (name "unconnected-(IC2-A1-Pad7)") (class "Default")
      (node (ref "IC2") (pin "7") (pinfunction "A1_7") (pintype "input"))
    )
    (net (code "62") (name "unconnected-(IC2-A2-Pad9)") (class "Default")
      (node (ref "IC2") (pin "9") (pinfunction "A2_9") (pintype "input"))
    )
    (net (code "63") (name "unconnected-(IC2-P0-Pad10)") (class "Default")
      (node (ref "IC2") (pin "10") (pinfunction "P0_10") (pintype "bidirectional"))
    )
    (net (code "64") (name "unconnected-(IC2-P1-Pad11)") (class "Default")
      (node (ref "IC2") (pin "11") (pinfunction "P1_11") (pintype "bidirectional"))
    )
    (net (code "65") (name "unconnected-(IC2-P2-Pad12)") (class "Default")
      (node (ref "IC2") (pin "12") (pinfunction "P2_12") (pintype "bidirectional"))
    )
    (net (code "66") (name "unconnected-(IC2-P3-Pad14)") (class "Default")
      (node (ref "IC2") (pin "14") (pinfunction "P3_14") (pintype "bidirectional"))
    )
    (net (code "67") (name "unconnected-(IC2-P4-Pad16)") (class "Default")
      (node (ref "IC2") (pin "16") (pinfunction "P4_16") (pintype "bidirectional"))
    )
    (net (code "68") (name "unconnected-(IC2-P5-Pad17)") (class "Default")
      (node (ref "IC2") (pin "17") (pinfunction "P5_17") (pintype "bidirectional"))
    )
    (net (code "69") (name "unconnected-(IC2-P6-Pad19)") (class "Default")
      (node (ref "IC2") (pin "19") (pinfunction "P6_19") (pintype "bidirectional"))
    )
    (net (code "70") (name "unconnected-(IC2-~{INT}-Pad1)") (class "Default")
      (node (ref "IC2") (pin "1") (pinfunction "~{INT}_1") (pintype "output"))
    )
    (net (code "71") (name "unconnected-(R21-Pad2)") (class "Default")
      (node (ref "R21") (pin "2") (pinfunction "2_2") (pintype "passive"))
    )
    (net (code "72") (name "unconnected-(U$1-DIO2-PadB1)") (class "Default")
      (node (ref "U$1") (pin "B1") (pinfunction "DIO2_B1") (pintype "bidirectional"))
    )
    (net (code "73") (name "unconnected-(U$1-DIO3-PadB6)") (class "Default")
      (node (ref "U$1") (pin "B6") (pinfunction "DIO3_B6") (pintype "bidirectional"))
    )
    (net (code "74") (name "unconnected-(U$1-DIO4-PadB5)") (class "Default")
      (node (ref "U$1") (pin "B5") (pinfunction "DIO4_B5") (pintype "bidirectional"))
    )
    (net (code "75") (name "unconnected-(U$1-DIO5-PadA7)") (class "Default")
      (node (ref "U$1") (pin "A7") (pinfunction "DIO5_A7") (pintype "bidirectional"))
    )
    (net (code "76") (name "unconnected-(U$2-2-PadP2)") (class "Default")
      (node (ref "U$2") (pin "P2") (pinfunction "2_P2") (pintype "bidirectional"))
    )
    (net (code "77") (name "unconnected-(U$2-5-PadP5)") (class "Default")
      (node (ref "U$2") (pin "P5") (pinfunction "5_P5") (pintype "bidirectional"))
    )
    (net (code "78") (name "unconnected-(U1-*GPIO9-PadGPIO9)") (class "Default")
      (node (ref "U1") (pin "GPIO9") (pinfunction "*GPIO9_GPIO9") (pintype "bidirectional"))
    )
    (net (code "79") (name "unconnected-(U1-*GPIO10-PadGPIO10)") (class "Default")
      (node (ref "U1") (pin "GPIO10") (pinfunction "*GPIO10_GPIO10") (pintype "bidirectional"))
    )
    (net (code "80") (name "unconnected-(U1-PadADC)") (class "Default")
      (node (ref "U1") (pin "ADC") (pinfunction "ADC_ADC") (pintype "bidirectional"))
    )
    (net (code "81") (name "unconnected-(U1-PadCS0)") (class "Default")
      (node (ref "U1") (pin "CS0") (pinfunction "CS0_CS0") (pintype "bidirectional"))
    )
    (net (code "82") (name "unconnected-(U1-PadMISO)") (class "Default")
      (node (ref "U1") (pin "MISO") (pinfunction "MISO_MISO") (pintype "bidirectional"))
    )
    (net (code "83") (name "unconnected-(U1-PadMOSI)") (class "Default")
      (node (ref "U1") (pin "MOSI") (pinfunction "MOSI_MOSI") (pintype "bidirectional"))
    )
    (net (code "84") (name "unconnected-(U1-PadSCLK)") (class "Default")
      (node (ref "U1") (pin "SCLK") (pinfunction "SCLK_SCLK") (pintype "bidirectional"))
    )
    (net (code "85") (name "unconnected-(U2-USBID-PadID1)") (class "Default")
      (node (ref "U2") (pin "ID1") (pinfunction "USBID_ID1") (pintype "bidirectional"))
    )
    (net (code "86") (name "unconnected-(U3-SELMPP0-Pad8)") (class "Default")
      (node (ref "U3") (pin "8") (pinfunction "SELMPP0_8") (pintype "input"))
    )
    (net (code "87") (name "unconnected-(U3-SELMPP1-Pad7)") (class "Default")
      (node (ref "U3") (pin "7") (pinfunction "SELMPP1_7") (pintype "input"))
    )
    (net (code "88") (name "unconnected-(U3-SET_CHRDY-Pad23)") (class "Default")
      (node (ref "U3") (pin "23") (pinfunction "SET_CHRDY_23") (pintype "bidirectional"))
    )
    (net (code "89") (name "unconnected-(U3-SET_OVCH-Pad22)") (class "Default")
      (node (ref "U3") (pin "22") (pinfunction "SET_OVCH_22") (pintype "bidirectional"))
    )
    (net (code "90") (name "unconnected-(U3-SET_OVDIS-Pad24)") (class "Default")
      (node (ref "U3") (pin "24") (pinfunction "SET_OVDIS_24") (pintype "bidirectional"))
    )
    (net (code "91") (name "unconnected-(U3-STATUS0-Pad21)") (class "Default")
      (node (ref "U3") (pin "21") (pinfunction "STATUS0_21") (pintype "output"))
    )
    (net (code "92") (name "unconnected-(U3-STATUS1-Pad20)") (class "Default")
      (node (ref "U3") (pin "20") (pinfunction "STATUS1_20") (pintype "output"))
    )
    (net (code "93") (name "unconnected-(U3-STATUS2-Pad19)") (class "Default")
      (node (ref "U3") (pin "19") (pinfunction "STATUS2_19") (pintype "output"))
    )
    (net (code "94") (name "unconnected-(U5-CRITICAL-Pad9)") (class "Default")
      (node (ref "U5") (pin "9") (pinfunction "CRITICAL_9") (pintype "output"))
    )
    (net (code "95") (name "unconnected-(U5-EPAD-Pad17)") (class "Default")
      (node (ref "U5") (pin "17") (pinfunction "EPAD_17") (pintype "passive"))
    )
    (net (code "96") (name "unconnected-(U5-PV-Pad10)") (class "Default")
      (node (ref "U5") (pin "10") (pinfunction "PV_10") (pintype "output"))
    )
    (net (code "97") (name "unconnected-(U5-TC-Pad13)") (class "Default")
      (node (ref "U5") (pin "13") (pinfunction "TC_13") (pintype "output"))
    )
    (net (code "98") (name "unconnected-(U5-WARNING-Pad8)") (class "Default")
      (node (ref "U5") (pin "8") (pinfunction "WARNING_8") (pintype "output"))
    )
    (net (code "99") (name "unconnected-(U6-ALERT-Pad2)") (class "Default")
      (node (ref "U6") (pin "2") (pinfunction "ALERT_2") (pintype "bidirectional"))
    )
  )
)
